# RPi_Motor_Driver_Rev_0_2.net
KiCad netlist of a schematic drawn in Altium Designer
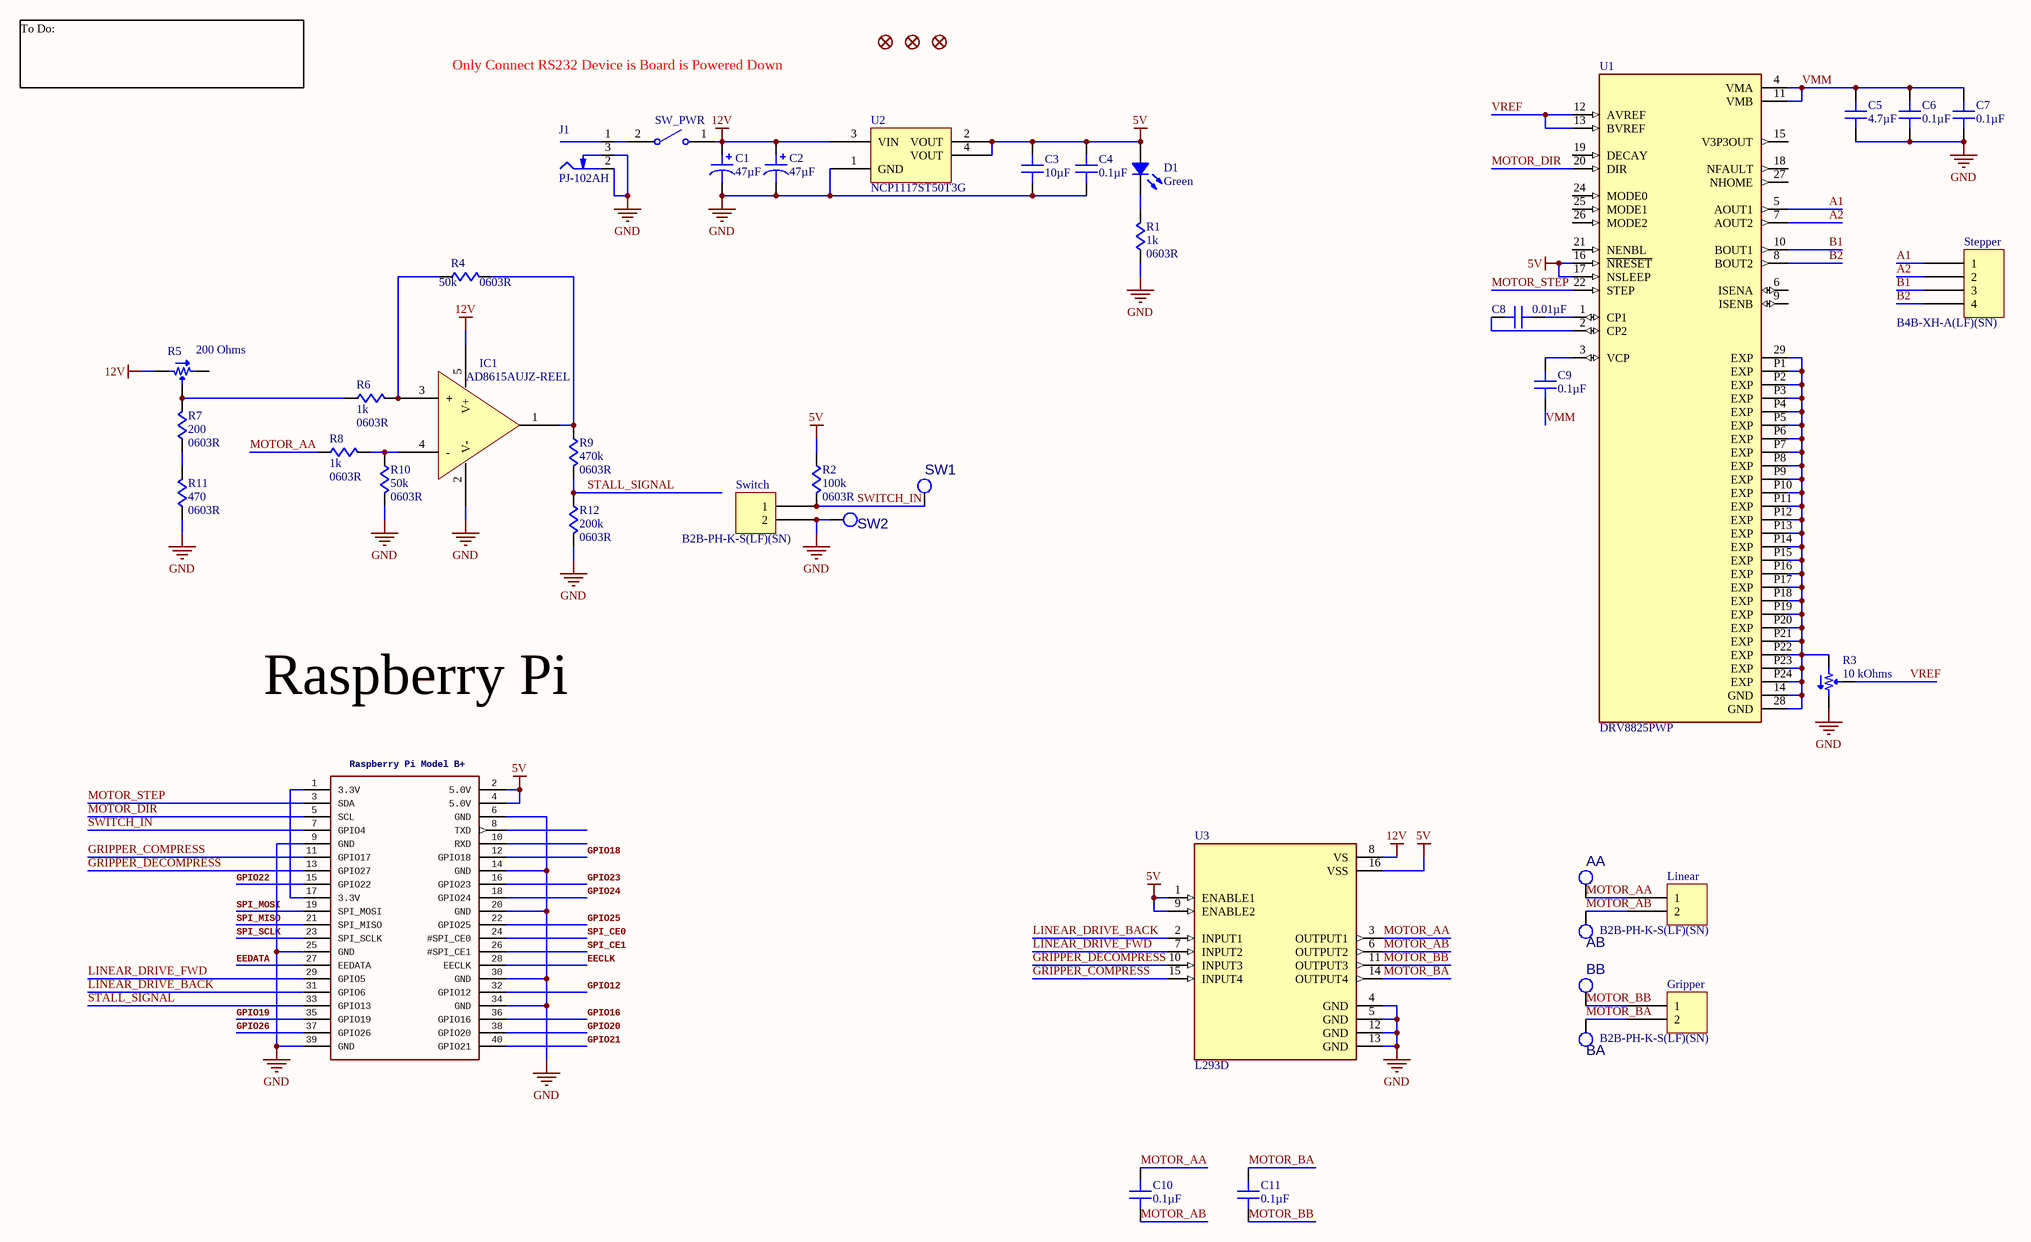
[diagram p0: RPi Motor Driver Rev 0.2.SchDoc]

(export (version "E")
  (design (tool "Eeschema 10.0.6"))
  (components
    (comp (ref "AA")
      (value "TH_Testpoint_40mil")
      (footprint "TH_Testpoint_40mil")
      (description "TH Testpoint")
      (libsource (lib "Testpoint") (part "TH_Testpoint_40mil"))
    )
    (comp (ref "AB")
      (value "TH_Testpoint_40mil")
      (footprint "TH_Testpoint_40mil")
      (description "TH Testpoint")
      (libsource (lib "Testpoint") (part "TH_Testpoint_40mil"))
    )
    (comp (ref "BA")
      (value "TH_Testpoint_40mil")
      (footprint "TH_Testpoint_40mil")
      (description "TH Testpoint")
      (libsource (lib "Testpoint") (part "TH_Testpoint_40mil"))
    )
    (comp (ref "BB")
      (value "TH_Testpoint_40mil")
      (footprint "TH_Testpoint_40mil")
      (description "TH Testpoint")
      (libsource (lib "Testpoint") (part "TH_Testpoint_40mil"))
    )
    (comp (ref "C1")
      (value "47µF")
      (footprint "CAP ALSMD 6.6MM H6.1MM")
      (description "CAP ALUM 47UF 20% 35V SMD")
      (fields (field (name "PART NUMBER") "EEE-FP1V470AP") (field (name "MANUFACTURER") "Nichicon"))
      (libsource (lib "Celestial Altium Library - altium_library") (part "Polarised Capacitor"))
    )
    (comp (ref "C2")
      (value "47µF")
      (footprint "CAP ALSMD 6.6MM H6.1MM")
      (description "CAP ALUM 47UF 20% 35V SMD")
      (fields (field (name "PART NUMBER") "EEE-FP1V470AP") (field (name "MANUFACTURER") "Nichicon"))
      (libsource (lib "Celestial Altium Library - altium_library") (part "Polarised Capacitor"))
    )
    (comp (ref "C3")
      (value "10µF")
      (footprint "CAP 0805_2012")
      (description "CAP CER 10UF 25V X5R 0805")
      (fields
        (field (name "PART NUMBER") "C2012X5R1E106K085AC")
        (field (name "MANUFACTURER") "TDK Corporation")
      )
      (libsource (lib "Celestial Altium Library - altium_library") (part "Capacitor"))
    )
    (comp (ref "C4")
      (value "0.1µF")
      (footprint "CAP 0603_1608")
      (description "CAP CER 0.1UF 50V X7R 0603")
      (fields
        (field (name "PART NUMBER") "CGA3E2X7R1H104K080AE")
        (field (name "MANUFACTURER") "TDK Corporation")
      )
      (libsource (lib "Celestial Altium Library - altium_library") (part "Capacitor"))
    )
    (comp (ref "C5")
      (value "4.7µF")
      (footprint "CAP 0603_1608")
      (description "CAP CER 4.7UF 35V X5R 0603")
      (fields
        (field (name "PART NUMBER") "C1608X5R1V475M080AC")
        (field (name "MANUFACTURER") "TDK Corporation")
      )
      (libsource (lib "Celestial Altium Library - altium_library") (part "Capacitor"))
    )
    (comp (ref "C6")
      (value "0.1µF")
      (footprint "CAP 0603_1608")
      (description "CAP CER 0.1UF 50V X7R 0603")
      (fields
        (field (name "PART NUMBER") "CGA3E2X7R1H104K080AE")
        (field (name "MANUFACTURER") "TDK Corporation")
      )
      (libsource (lib "Celestial Altium Library - altium_library") (part "Capacitor"))
    )
    (comp (ref "C7")
      (value "0.1µF")
      (footprint "CAP 0603_1608")
      (description "CAP CER 0.1UF 50V X7R 0603")
      (fields
        (field (name "PART NUMBER") "CGA3E2X7R1H104K080AE")
        (field (name "MANUFACTURER") "TDK Corporation")
      )
      (libsource (lib "Celestial Altium Library - altium_library") (part "Capacitor"))
    )
    (comp (ref "C8")
      (value "0.01µF")
      (footprint "CAP 0603_1608")
      (description "CAP CER 0.01UF 250V X7R 0603")
      (fields (field (name "PART NUMBER") "C0603C103KARACAUTO") (field (name "MANUFACTURER") "KEMET"))
      (libsource (lib "Celestial Altium Library - altium_library") (part "Capacitor"))
    )
    (comp (ref "C9")
      (value "0.1µF")
      (footprint "CAP 0603_1608")
      (description "CAP CER 0.1UF 50V X7R 0603")
      (fields
        (field (name "PART NUMBER") "CGA3E2X7R1H104K080AE")
        (field (name "MANUFACTURER") "TDK Corporation")
      )
      (libsource (lib "Celestial Altium Library - altium_library") (part "Capacitor"))
    )
    (comp (ref "C10")
      (value "0.1µF")
      (footprint "CAP 0603_1608")
      (description "CAP CER 0.1UF 50V X7R 0603")
      (fields
        (field (name "PART NUMBER") "CGA3E2X7R1H104K080AE")
        (field (name "MANUFACTURER") "TDK Corporation")
      )
      (libsource (lib "Celestial Altium Library - altium_library") (part "Capacitor"))
    )
    (comp (ref "C11")
      (value "0.1µF")
      (footprint "CAP 0603_1608")
      (description "CAP CER 0.1UF 50V X7R 0603")
      (fields
        (field (name "PART NUMBER") "CGA3E2X7R1H104K080AE")
        (field (name "MANUFACTURER") "TDK Corporation")
      )
      (libsource (lib "Celestial Altium Library - altium_library") (part "Capacitor"))
    )
    (comp (ref "D1")
      (value "Green")
      (footprint "LED 0603_1608 GREEN")
      (description "LED GREEN CLEAR 1608 SMD")
      (fields (field (name "PART NUMBER") "APT1608CGCK") (field (name "MANUFACTURER") "Kingbright"))
      (libsource (lib "Celestial Altium Library - altium_library") (part "LED"))
    )
    (comp (ref "FID1")
      (value "FIDUCIAL\"\"")
      (footprint "FIDUCIAL_1MM")
      (description "Fiducial Alignment PointsVarious fiducial points for machine vision alignment.")
      (libsource (lib "microbuilder") (part "FIDUCIAL{dblquote}{dblquote}"))
    )
    (comp (ref "FID2")
      (value "FIDUCIAL\"\"")
      (footprint "FIDUCIAL_1MM")
      (description "Fiducial Alignment PointsVarious fiducial points for machine vision alignment.")
      (libsource (lib "microbuilder") (part "FIDUCIAL{dblquote}{dblquote}"))
    )
    (comp (ref "FID3")
      (value "FIDUCIAL\"\"")
      (footprint "FIDUCIAL_1MM")
      (description "Fiducial Alignment PointsVarious fiducial points for machine vision alignment.")
      (libsource (lib "microbuilder") (part "FIDUCIAL{dblquote}{dblquote}"))
    )
    (comp (ref "Gripper")
      (value "B2B-PH-K-S(LF)(SN)")
      (footprint "JST B2B-PH-K")
      (description "CONN HEADER VERT 2POS 2MM")
      (fields (field (name "MANUFACTURER") "JST Sales America Inc."))
      (libsource (lib "Celestial Altium Library - altium_library") (part "2 Pin"))
    )
    (comp (ref "IC1")
      (value "AD8615AUJZ-REEL")
      (footprint "ANALOG TSOT-23-5 UJ-5")
      (description "IC OPAMP GP 1 CIRCUIT TSOT23-5")
      (fields (field (name "MANUFACTURER") "Analog Devices Inc."))
      (libsource (lib "Celestial Altium Library - altium_library") (part "ANALOG DEV AD8615AUJZ"))
    )
    (comp (ref "J1")
      (value "PJ-102AH")
      (footprint "CUI PJ-102AH")
      (description "CONN PWR JACK 2X5.5MM SOLDER")
      (fields (field (name "MANUFACTURER") "CUI Devices"))
      (libsource (lib "Celestial Altium Library - altium_library") (part "Barrel Connector"))
    )
    (comp (ref "Linear")
      (value "B2B-PH-K-S(LF)(SN)")
      (footprint "JST B2B-PH-K")
      (description "CONN HEADER VERT 2POS 2MM")
      (fields (field (name "MANUFACTURER") "JST Sales America Inc."))
      (libsource (lib "Celestial Altium Library - altium_library") (part "2 Pin"))
    )
    (comp (ref "R1")
      (value "1k")
      (footprint "0603R")
      (fields (field (name "Comment") "Resistor 0603"))
      (libsource (lib "MikesAltiumLibrary") (part "Resistor"))
    )
    (comp (ref "R2")
      (value "100k")
      (footprint "0603R")
      (fields (field (name "Comment") "Resistor 0603"))
      (libsource (lib "MikesAltiumLibrary") (part "Resistor"))
    )
    (comp (ref "R3")
      (value "10 kOhms")
      (footprint "POT BOURNS TRIMPOT TC33")
      (description "TRIMMER 10K OHM 0.1W J LEAD TOP")
      (fields (field (name "PART NUMBER") "TC33X-2-103E") (field (name "MANUFACTURER") "Bourns Inc."))
      (libsource (lib "Celestial Altium Library - altium_library") (part "Potentiometer"))
    )
    (comp (ref "R4")
      (value "50k")
      (footprint "0603R")
      (fields (field (name "Comment") "Resistor 0603"))
      (libsource (lib "MikesAltiumLibrary") (part "Resistor"))
    )
    (comp (ref "R5")
      (value "200 Ohms")
      (footprint "POT BOURNS TRIMPOT TC33")
      (description "TRIMMER 200 OHM 0.1W J LEAD TOP")
      (fields (field (name "PART NUMBER") "TC33X-2-201E") (field (name "MANUFACTURER") "Bourns Inc."))
      (libsource (lib "Celestial Altium Library - altium_library") (part "Potentiometer"))
    )
    (comp (ref "R6")
      (value "1k")
      (footprint "0603R")
      (fields (field (name "Comment") "Resistor 0603"))
      (libsource (lib "MikesAltiumLibrary") (part "Resistor"))
    )
    (comp (ref "R7")
      (value "200")
      (footprint "0603R")
      (fields (field (name "Comment") "Resistor 0603"))
      (libsource (lib "MikesAltiumLibrary") (part "Resistor"))
    )
    (comp (ref "R8")
      (value "1k")
      (footprint "0603R")
      (fields (field (name "Comment") "Resistor 0603"))
      (libsource (lib "MikesAltiumLibrary") (part "Resistor"))
    )
    (comp (ref "R9")
      (value "470k")
      (footprint "0603R")
      (fields (field (name "Comment") "Resistor 0603"))
      (libsource (lib "MikesAltiumLibrary") (part "Resistor"))
    )
    (comp (ref "R10")
      (value "50k")
      (footprint "0603R")
      (fields (field (name "Comment") "Resistor 0603"))
      (libsource (lib "MikesAltiumLibrary") (part "Resistor"))
    )
    (comp (ref "R11")
      (value "470")
      (footprint "0603R")
      (fields (field (name "Comment") "Resistor 0603"))
      (libsource (lib "MikesAltiumLibrary") (part "Resistor"))
    )
    (comp (ref "R12")
      (value "200k")
      (footprint "0603R")
      (fields (field (name "Comment") "Resistor 0603"))
      (libsource (lib "MikesAltiumLibrary") (part "Resistor"))
    )
    (comp (ref "RPI1")
      (value "RASPBERRYPI_BPLUS_HATSLOTS")
      (footprint "PI_HAT_SLOTS")
      (fields (field (name "RASPBERRYPIMODELB+") "Raspberry Pi Model B+"))
      (libsource (lib "microbuilder") (part "RASPBERRYPI_BPLUS_HATSLOTS"))
    )
    (comp (ref "Stepper")
      (value "B4B-XH-A(LF)(SN)")
      (footprint "JST XH B4B-XH-A")
      (description "CONN HEADER VERT 4POS 2.5MM")
      (fields (field (name "MANUFACTURER") "JST Sales America Inc."))
      (libsource (lib "Celestial Altium Library - altium_library") (part "4 Pin"))
    )
    (comp (ref "SW1")
      (value "TH_Testpoint_40mil")
      (footprint "TH_Testpoint_40mil")
      (description "TH Testpoint")
      (libsource (lib "Testpoint") (part "TH_Testpoint_40mil"))
    )
    (comp (ref "SW2")
      (value "TH_Testpoint_40mil")
      (footprint "TH_Testpoint_40mil")
      (description "TH Testpoint")
      (libsource (lib "Testpoint") (part "TH_Testpoint_40mil"))
    )
    (comp (ref "Switch")
      (value "B2B-PH-K-S(LF)(SN)")
      (footprint "JST B2B-PH-K")
      (description "CONN HEADER VERT 2POS 2MM")
      (fields (field (name "MANUFACTURER") "JST Sales America Inc."))
      (libsource (lib "") (part "2 Pin_1"))
    )
    (comp (ref "SW_PWR")
      (value "500SSP1S2M2QEA")
      (footprint "SWITCH SLIDE SPDT 5A 125V")
      (description "SWITCH SLIDE SPDT 5A 125V")
      (libsource (lib "MikesAltiumLibrary") (part "SWITCH SLIDE SPDT 5A 125V"))
    )
    (comp (ref "U1")
      (value "DRV8825PWP")
      (footprint "SOP65P640X120-29N")
      (description "Bipolar Motor Driver Power MOSFET Logic 28-HTSSOP")
      (libsource (lib "MikesAltiumLibrary") (part "DRV8825PWP"))
    )
    (comp (ref "U2")
      (value "NCP1117ST50T3G")
      (footprint "ON SEMI SOT-223 ST(318H)")
      (description "IC REG LINEAR 5V 1A SOT223")
      (fields (field (name "MANUFACTURER") "ON Semiconductor"))
      (libsource (lib "Celestial Altium Library - altium_library") (part "ON Semi NCP1117"))
    )
    (comp (ref "U3")
      (value "L293D")
      (footprint "DIP880W50P254L2000H510Q16")
      (description "Bipolar Motor Driver Parallel 16-PowerDIP")
      (libsource (lib "MikesAltiumLibrary") (part "L293D"))
    )
  )
  (nets
    (net (code "1") (name "/A1") (class "Default")
      (node (ref "Stepper") (pin "1") (pinfunction "1_1") (pintype "passive"))
      (node (ref "U1") (pin "5") (pinfunction "AOUT1_5") (pintype "output"))
    )
    (net (code "2") (name "/A2") (class "Default")
      (node (ref "Stepper") (pin "2") (pinfunction "2_2") (pintype "passive"))
      (node (ref "U1") (pin "7") (pinfunction "AOUT2_7") (pintype "output"))
    )
    (net (code "3") (name "/B1") (class "Default")
      (node (ref "Stepper") (pin "3") (pinfunction "3_3") (pintype "passive"))
      (node (ref "U1") (pin "10") (pinfunction "BOUT1_10") (pintype "output"))
    )
    (net (code "4") (name "/B2") (class "Default")
      (node (ref "Stepper") (pin "4") (pinfunction "4_4") (pintype "passive"))
      (node (ref "U1") (pin "8") (pinfunction "BOUT2_8") (pintype "output"))
    )
    (net (code "5") (name "/EECLK") (class "Default")
      (node (ref "RPI1") (pin "28") (pinfunction "EECLK_28") (pintype "open_emitter"))
    )
    (net (code "6") (name "/EEDATA") (class "Default")
      (node (ref "RPI1") (pin "27") (pinfunction "EEDATA_27") (pintype "passive"))
    )
    (net (code "7") (name "/GPIO12") (class "Default")
      (node (ref "RPI1") (pin "32") (pinfunction "GPIO12_32") (pintype "passive"))
    )
    (net (code "8") (name "/GPIO16") (class "Default")
      (node (ref "RPI1") (pin "36") (pinfunction "GPIO16_36") (pintype "open_emitter"))
    )
    (net (code "9") (name "/GPIO18") (class "Default")
      (node (ref "RPI1") (pin "12") (pinfunction "GPIO18_12") (pintype "passive"))
    )
    (net (code "10") (name "/GPIO19") (class "Default")
      (node (ref "RPI1") (pin "35") (pinfunction "GPIO19_35") (pintype "passive"))
    )
    (net (code "11") (name "/GPIO20") (class "Default")
      (node (ref "RPI1") (pin "38") (pinfunction "GPIO20_38") (pintype "passive"))
    )
    (net (code "12") (name "/GPIO21") (class "Default")
      (node (ref "RPI1") (pin "40") (pinfunction "GPIO21_40") (pintype "passive"))
    )
    (net (code "13") (name "/GPIO22") (class "Default")
      (node (ref "RPI1") (pin "15") (pinfunction "GPIO22_15") (pintype "passive"))
    )
    (net (code "14") (name "/GPIO23") (class "Default")
      (node (ref "RPI1") (pin "16") (pinfunction "GPIO23_16") (pintype "passive"))
    )
    (net (code "15") (name "/GPIO24") (class "Default")
      (node (ref "RPI1") (pin "18") (pinfunction "GPIO24_18") (pintype "passive"))
    )
    (net (code "16") (name "/GPIO25") (class "Default")
      (node (ref "RPI1") (pin "22") (pinfunction "GPIO25_22") (pintype "passive"))
    )
    (net (code "17") (name "/GPIO26") (class "Default")
      (node (ref "RPI1") (pin "37") (pinfunction "GPIO26_37") (pintype "passive"))
    )
    (net (code "18") (name "/GRIPPER_COMPRESS") (class "Default")
      (node (ref "RPI1") (pin "11") (pinfunction "GPIO17_11") (pintype "passive"))
      (node (ref "U3") (pin "15") (pinfunction "INPUT4_15") (pintype "input"))
    )
    (net (code "19") (name "/GRIPPER_DECOMPRESS") (class "Default")
      (node (ref "RPI1") (pin "13") (pinfunction "GPIO27_13") (pintype "passive"))
      (node (ref "U3") (pin "10") (pinfunction "INPUT3_10") (pintype "input"))
    )
    (net (code "20") (name "/LINEAR_DRIVE_BACK") (class "Default")
      (node (ref "RPI1") (pin "31") (pinfunction "GPIO6_31") (pintype "open_emitter"))
      (node (ref "U3") (pin "2") (pinfunction "INPUT1_2") (pintype "input"))
    )
    (net (code "21") (name "/LINEAR_DRIVE_FWD") (class "Default")
      (node (ref "RPI1") (pin "29") (pinfunction "GPIO5_29") (pintype "passive"))
      (node (ref "U3") (pin "7") (pinfunction "INPUT2_7") (pintype "input"))
    )
    (net (code "22") (name "/MOTOR_AA") (class "Default")
      (node (ref "AA") (pin "1") (pinfunction "1_1") (pintype "passive"))
      (node (ref "C10") (pin "2") (pinfunction "2_2") (pintype "passive"))
      (node (ref "Linear") (pin "1") (pinfunction "1_1") (pintype "passive"))
      (node (ref "R8") (pin "2") (pinfunction "2_2") (pintype "power_in"))
      (node (ref "U3") (pin "3") (pinfunction "OUTPUT1_3") (pintype "output"))
    )
    (net (code "23") (name "/MOTOR_AB") (class "Default")
      (node (ref "AB") (pin "1") (pinfunction "1_1") (pintype "passive"))
      (node (ref "C10") (pin "1") (pinfunction "1_1") (pintype "passive"))
      (node (ref "Linear") (pin "2") (pinfunction "2_2") (pintype "passive"))
      (node (ref "U3") (pin "6") (pinfunction "OUTPUT2_6") (pintype "output"))
    )
    (net (code "24") (name "/MOTOR_BA") (class "Default")
      (node (ref "BA") (pin "1") (pinfunction "1_1") (pintype "passive"))
      (node (ref "C11") (pin "2") (pinfunction "2_2") (pintype "passive"))
      (node (ref "Gripper") (pin "2") (pinfunction "2_2") (pintype "passive"))
      (node (ref "U3") (pin "14") (pinfunction "OUTPUT4_14") (pintype "output"))
    )
    (net (code "25") (name "/MOTOR_BB") (class "Default")
      (node (ref "BB") (pin "1") (pinfunction "1_1") (pintype "passive"))
      (node (ref "C11") (pin "1") (pinfunction "1_1") (pintype "passive"))
      (node (ref "Gripper") (pin "1") (pinfunction "1_1") (pintype "passive"))
      (node (ref "U3") (pin "11") (pinfunction "OUTPUT3_11") (pintype "output"))
    )
    (net (code "26") (name "/MOTOR_DIR") (class "Default")
      (node (ref "RPI1") (pin "5") (pinfunction "SCL_5") (pintype "passive"))
      (node (ref "U1") (pin "20") (pinfunction "DIR_20") (pintype "input"))
    )
    (net (code "27") (name "/MOTOR_STEP") (class "Default")
      (node (ref "RPI1") (pin "3") (pinfunction "SDA_3") (pintype "passive"))
      (node (ref "U1") (pin "22") (pinfunction "STEP_22") (pintype "input"))
    )
    (net (code "28") (name "/SPI_CE0") (class "Default")
      (node (ref "RPI1") (pin "24") (pinfunction "#SPI_CE0_24") (pintype "passive"))
    )
    (net (code "29") (name "/SPI_CE1") (class "Default")
      (node (ref "RPI1") (pin "26") (pinfunction "#SPI_CE1_26") (pintype "passive"))
    )
    (net (code "30") (name "/SPI_MISO") (class "Default")
      (node (ref "RPI1") (pin "21") (pinfunction "SPI_MISO_21") (pintype "passive"))
    )
    (net (code "31") (name "/SPI_MOSI") (class "Default")
      (node (ref "RPI1") (pin "19") (pinfunction "SPI_MOSI_19") (pintype "passive"))
    )
    (net (code "32") (name "/SPI_SCLK") (class "Default")
      (node (ref "RPI1") (pin "23") (pinfunction "SPI_SCLK_23") (pintype "passive"))
    )
    (net (code "33") (name "/STALL_SIGNAL") (class "Default")
      (node (ref "R12") (pin "2") (pinfunction "2_2") (pintype "power_in"))
      (node (ref "R9") (pin "1") (pinfunction "1_1") (pintype "power_in"))
      (node (ref "RPI1") (pin "33") (pinfunction "GPIO13_33") (pintype "passive"))
    )
    (net (code "34") (name "/SWITCH_IN") (class "Default")
      (node (ref "R2") (pin "1") (pinfunction "1_1") (pintype "power_in"))
      (node (ref "RPI1") (pin "7") (pinfunction "GPIO4_7") (pintype "passive"))
      (node (ref "SW1") (pin "1") (pinfunction "1_1") (pintype "passive"))
      (node (ref "Switch") (pin "1") (pinfunction "1_1") (pintype "passive"))
    )
    (net (code "35") (name "/VMM") (class "Default")
      (node (ref "C5") (pin "2") (pinfunction "2_2") (pintype "passive"))
      (node (ref "C6") (pin "2") (pinfunction "2_2") (pintype "passive"))
      (node (ref "C7") (pin "2") (pinfunction "2_2") (pintype "passive"))
      (node (ref "C9") (pin "1") (pinfunction "1_1") (pintype "passive"))
      (node (ref "U1") (pin "11") (pinfunction "VMB_11") (pintype "power_in"))
      (node (ref "U1") (pin "4") (pinfunction "VMA_4") (pintype "power_in"))
    )
    (net (code "36") (name "/VREF") (class "Default")
      (node (ref "R3") (pin "2") (pinfunction "2_2") (pintype "passive"))
      (node (ref "U1") (pin "12") (pinfunction "AVREF_12") (pintype "input"))
      (node (ref "U1") (pin "13") (pinfunction "BVREF_13") (pintype "input"))
    )
    (net (code "37") (name "5V") (class "Default")
      (node (ref "C3") (pin "2") (pinfunction "2_2") (pintype "passive"))
      (node (ref "C4") (pin "2") (pinfunction "2_2") (pintype "passive"))
      (node (ref "D1") (pin "1") (pinfunction "1_1") (pintype "passive"))
      (node (ref "R2") (pin "2") (pinfunction "2_2") (pintype "power_in"))
      (node (ref "RPI1") (pin "2") (pinfunction "5.0V_2") (pintype "open_emitter"))
      (node (ref "RPI1") (pin "4") (pinfunction "5.0V_4") (pintype "open_emitter"))
      (node (ref "U1") (pin "16") (pinfunction "~{NRESET}_16") (pintype "input"))
      (node (ref "U1") (pin "17") (pinfunction "NSLEEP_17") (pintype "input"))
      (node (ref "U2") (pin "2") (pinfunction "VOUT_2") (pintype "passive"))
      (node (ref "U2") (pin "4") (pinfunction "VOUT_4") (pintype "passive"))
      (node (ref "U3") (pin "1") (pinfunction "ENABLE1_1") (pintype "input"))
      (node (ref "U3") (pin "16") (pinfunction "VSS_16") (pintype "power_in"))
      (node (ref "U3") (pin "9") (pinfunction "ENABLE2_9") (pintype "input"))
    )
    (net (code "38") (name "12V") (class "Default")
      (node (ref "C1") (pin "1") (pinfunction "1_1") (pintype "passive"))
      (node (ref "C2") (pin "1") (pinfunction "1_1") (pintype "passive"))
      (node (ref "IC1") (pin "5") (pinfunction "V+_5") (pintype "passive"))
      (node (ref "R5") (pin "1") (pinfunction "1_1") (pintype "passive"))
      (node (ref "SW_PWR") (pin "1") (pinfunction "1_1") (pintype "passive"))
      (node (ref "U2") (pin "3") (pinfunction "VIN_3") (pintype "passive"))
      (node (ref "U3") (pin "8") (pinfunction "VS_8") (pintype "power_in"))
    )
    (net (code "39") (name "GND") (class "Default")
      (node (ref "C1") (pin "2") (pinfunction "2_2") (pintype "passive"))
      (node (ref "C2") (pin "2") (pinfunction "2_2") (pintype "passive"))
      (node (ref "C3") (pin "1") (pinfunction "1_1") (pintype "passive"))
      (node (ref "C4") (pin "1") (pinfunction "1_1") (pintype "passive"))
      (node (ref "C5") (pin "1") (pinfunction "1_1") (pintype "passive"))
      (node (ref "C6") (pin "1") (pinfunction "1_1") (pintype "passive"))
      (node (ref "C7") (pin "1") (pinfunction "1_1") (pintype "passive"))
      (node (ref "IC1") (pin "2") (pinfunction "V-_2") (pintype "passive"))
      (node (ref "J1") (pin "2") (pinfunction "Outer_2") (pintype "passive"))
      (node (ref "J1") (pin "3") (pinfunction "SW_3") (pintype "passive"))
      (node (ref "R1") (pin "2") (pinfunction "2_2") (pintype "power_in"))
      (node (ref "R10") (pin "1") (pinfunction "1_1") (pintype "power_in"))
      (node (ref "R11") (pin "2") (pinfunction "2_2") (pintype "power_in"))
      (node (ref "R12") (pin "1") (pinfunction "1_1") (pintype "power_in"))
      (node (ref "R3") (pin "3") (pinfunction "3_3") (pintype "passive"))
      (node (ref "RPI1") (pin "14") (pinfunction "GND_14") (pintype "open_emitter"))
      (node (ref "RPI1") (pin "20") (pinfunction "GND_20") (pintype "open_emitter"))
      (node (ref "RPI1") (pin "25") (pinfunction "GND_25") (pintype "open_emitter"))
      (node (ref "RPI1") (pin "30") (pinfunction "GND_30") (pintype "passive"))
      (node (ref "RPI1") (pin "34") (pinfunction "GND_34") (pintype "passive"))
      (node (ref "RPI1") (pin "39") (pinfunction "GND_39") (pintype "open_emitter"))
      (node (ref "RPI1") (pin "6") (pinfunction "GND_6") (pintype "open_emitter"))
      (node (ref "RPI1") (pin "9") (pinfunction "GND_9") (pintype "open_emitter"))
      (node (ref "SW2") (pin "1") (pinfunction "1_1") (pintype "passive"))
      (node (ref "Switch") (pin "2") (pinfunction "2_2") (pintype "passive"))
      (node (ref "U2") (pin "1") (pinfunction "GND_1") (pintype "passive"))
      (node (ref "U3") (pin "12") (pinfunction "GND_12") (pintype "power_in"))
      (node (ref "U3") (pin "13") (pinfunction "GND_13") (pintype "power_in"))
      (node (ref "U3") (pin "4") (pinfunction "GND_4") (pintype "power_in"))
      (node (ref "U3") (pin "5") (pinfunction "GND_5") (pintype "power_in"))
    )
    (net (code "40") (name "Net-(D1-Pad2)") (class "Default")
      (node (ref "D1") (pin "2") (pinfunction "2_2") (pintype "passive"))
      (node (ref "R1") (pin "1") (pinfunction "1_1") (pintype "power_in"))
    )
    (net (code "41") (name "Net-(IC1-+)") (class "Default")
      (node (ref "IC1") (pin "3") (pinfunction "+_3") (pintype "passive"))
      (node (ref "R4") (pin "2") (pinfunction "2_2") (pintype "power_in"))
      (node (ref "R6") (pin "1") (pinfunction "1_1") (pintype "power_in"))
    )
    (net (code "42") (name "Net-(IC1--)") (class "Default")
      (node (ref "IC1") (pin "4") (pinfunction "-_4") (pintype "passive"))
      (node (ref "R10") (pin "2") (pinfunction "2_2") (pintype "power_in"))
      (node (ref "R8") (pin "1") (pinfunction "1_1") (pintype "power_in"))
    )
    (net (code "43") (name "Net-(IC1-OUT)") (class "Default")
      (node (ref "IC1") (pin "1") (pinfunction "OUT_1") (pintype "passive"))
      (node (ref "R4") (pin "1") (pinfunction "1_1") (pintype "power_in"))
      (node (ref "R9") (pin "2") (pinfunction "2_2") (pintype "power_in"))
    )
    (net (code "44") (name "Net-(J1-Centre)") (class "Default")
      (node (ref "J1") (pin "1") (pinfunction "Centre_1") (pintype "passive"))
      (node (ref "SW_PWR") (pin "2") (pinfunction "2_2") (pintype "passive"))
    )
    (net (code "45") (name "Net-(R3-Pad1)") (class "Default")
      (node (ref "R3") (pin "1") (pinfunction "1_1") (pintype "passive"))
      (node (ref "U1") (pin "14") (pinfunction "GND_14") (pintype "power_in"))
      (node (ref "U1") (pin "28") (pinfunction "GND_28") (pintype "power_in"))
      (node (ref "U1") (pin "29") (pinfunction "EXP_29") (pintype "power_in"))
      (node (ref "U1") (pin "P1") (pinfunction "EXP_P1") (pintype "power_in"))
      (node (ref "U1") (pin "P10") (pinfunction "EXP_P10") (pintype "power_in"))
      (node (ref "U1") (pin "P11") (pinfunction "EXP_P11") (pintype "power_in"))
      (node (ref "U1") (pin "P12") (pinfunction "EXP_P12") (pintype "power_in"))
      (node (ref "U1") (pin "P13") (pinfunction "EXP_P13") (pintype "power_in"))
      (node (ref "U1") (pin "P14") (pinfunction "EXP_P14") (pintype "power_in"))
      (node (ref "U1") (pin "P15") (pinfunction "EXP_P15") (pintype "power_in"))
      (node (ref "U1") (pin "P16") (pinfunction "EXP_P16") (pintype "power_in"))
      (node (ref "U1") (pin "P17") (pinfunction "EXP_P17") (pintype "power_in"))
      (node (ref "U1") (pin "P18") (pinfunction "EXP_P18") (pintype "power_in"))
      (node (ref "U1") (pin "P19") (pinfunction "EXP_P19") (pintype "power_in"))
      (node (ref "U1") (pin "P2") (pinfunction "EXP_P2") (pintype "power_in"))
      (node (ref "U1") (pin "P20") (pinfunction "EXP_P20") (pintype "power_in"))
      (node (ref "U1") (pin "P21") (pinfunction "EXP_P21") (pintype "power_in"))
      (node (ref "U1") (pin "P22") (pinfunction "EXP_P22") (pintype "power_in"))
      (node (ref "U1") (pin "P23") (pinfunction "EXP_P23") (pintype "power_in"))
      (node (ref "U1") (pin "P24") (pinfunction "EXP_P24") (pintype "power_in"))
      (node (ref "U1") (pin "P3") (pinfunction "EXP_P3") (pintype "power_in"))
      (node (ref "U1") (pin "P4") (pinfunction "EXP_P4") (pintype "power_in"))
      (node (ref "U1") (pin "P5") (pinfunction "EXP_P5") (pintype "power_in"))
      (node (ref "U1") (pin "P6") (pinfunction "EXP_P6") (pintype "power_in"))
      (node (ref "U1") (pin "P7") (pinfunction "EXP_P7") (pintype "power_in"))
      (node (ref "U1") (pin "P8") (pinfunction "EXP_P8") (pintype "power_in"))
      (node (ref "U1") (pin "P9") (pinfunction "EXP_P9") (pintype "power_in"))
    )
    (net (code "46") (name "Net-(R5-Pad2)") (class "Default")
      (node (ref "R5") (pin "2") (pinfunction "2_2") (pintype "passive"))
      (node (ref "R6") (pin "2") (pinfunction "2_2") (pintype "power_in"))
      (node (ref "R7") (pin "1") (pinfunction "1_1") (pintype "power_in"))
    )
    (net (code "47") (name "Net-(R11-Pad1)") (class "Default")
      (node (ref "R11") (pin "1") (pinfunction "1_1") (pintype "power_in"))
      (node (ref "R7") (pin "2") (pinfunction "2_2") (pintype "power_in"))
    )
    (net (code "48") (name "Net-(RPI1-3.3V-Pad1)") (class "Default")
      (node (ref "RPI1") (pin "1") (pinfunction "3.3V_1") (pintype "open_emitter"))
      (node (ref "RPI1") (pin "17") (pinfunction "3.3V_17") (pintype "open_emitter"))
    )
    (net (code "49") (name "Net-(U1-CP1)") (class "Default")
      (node (ref "C8") (pin "2") (pinfunction "2_2") (pintype "passive"))
      (node (ref "U1") (pin "1") (pinfunction "CP1_1") (pintype "bidirectional"))
    )
    (net (code "50") (name "Net-(U1-CP2)") (class "Default")
      (node (ref "C8") (pin "1") (pinfunction "1_1") (pintype "passive"))
      (node (ref "U1") (pin "2") (pinfunction "CP2_2") (pintype "bidirectional"))
    )
    (net (code "51") (name "Net-(U1-VCP)") (class "Default")
      (node (ref "C9") (pin "2") (pinfunction "2_2") (pintype "passive"))
      (node (ref "U1") (pin "3") (pinfunction "VCP_3") (pintype "bidirectional"))
    )
    (net (code "52") (name "unconnected-(R5-Pad3)") (class "Default")
      (node (ref "R5") (pin "3") (pinfunction "3_3") (pintype "passive"))
    )
    (net (code "53") (name "unconnected-(RPI1-RXD-Pad10)") (class "Default")
      (node (ref "RPI1") (pin "10") (pinfunction "RXD_10") (pintype "passive"))
    )
    (net (code "54") (name "unconnected-(RPI1-TXD-Pad8)") (class "Default")
      (node (ref "RPI1") (pin "8") (pinfunction "TXD_8") (pintype "output"))
    )
    (net (code "55") (name "unconnected-(U1-DECAY-Pad19)") (class "Default")
      (node (ref "U1") (pin "19") (pinfunction "DECAY_19") (pintype "input"))
    )
    (net (code "56") (name "unconnected-(U1-ISENA-Pad6)") (class "Default")
      (node (ref "U1") (pin "6") (pinfunction "ISENA_6") (pintype "bidirectional"))
    )
    (net (code "57") (name "unconnected-(U1-ISENB-Pad9)") (class "Default")
      (node (ref "U1") (pin "9") (pinfunction "ISENB_9") (pintype "bidirectional"))
    )
    (net (code "58") (name "unconnected-(U1-MODE0-Pad24)") (class "Default")
      (node (ref "U1") (pin "24") (pinfunction "MODE0_24") (pintype "input"))
    )
    (net (code "59") (name "unconnected-(U1-MODE1-Pad25)") (class "Default")
      (node (ref "U1") (pin "25") (pinfunction "MODE1_25") (pintype "input"))
    )
    (net (code "60") (name "unconnected-(U1-MODE2-Pad26)") (class "Default")
      (node (ref "U1") (pin "26") (pinfunction "MODE2_26") (pintype "input"))
    )
    (net (code "61") (name "unconnected-(U1-NENBL-Pad21)") (class "Default")
      (node (ref "U1") (pin "21") (pinfunction "NENBL_21") (pintype "input"))
    )
    (net (code "62") (name "unconnected-(U1-NFAULT-Pad18)") (class "Default")
      (node (ref "U1") (pin "18") (pinfunction "NFAULT_18") (pintype "output"))
    )
    (net (code "63") (name "unconnected-(U1-NHOME-Pad27)") (class "Default")
      (node (ref "U1") (pin "27") (pinfunction "NHOME_27") (pintype "output"))
    )
    (net (code "64") (name "unconnected-(U1-V3P3OUT-Pad15)") (class "Default")
      (node (ref "U1") (pin "15") (pinfunction "V3P3OUT_15") (pintype "output"))
    )
  )
)
